# Bawah.net
KiCad netlist of a schematic drawn in EAGLE
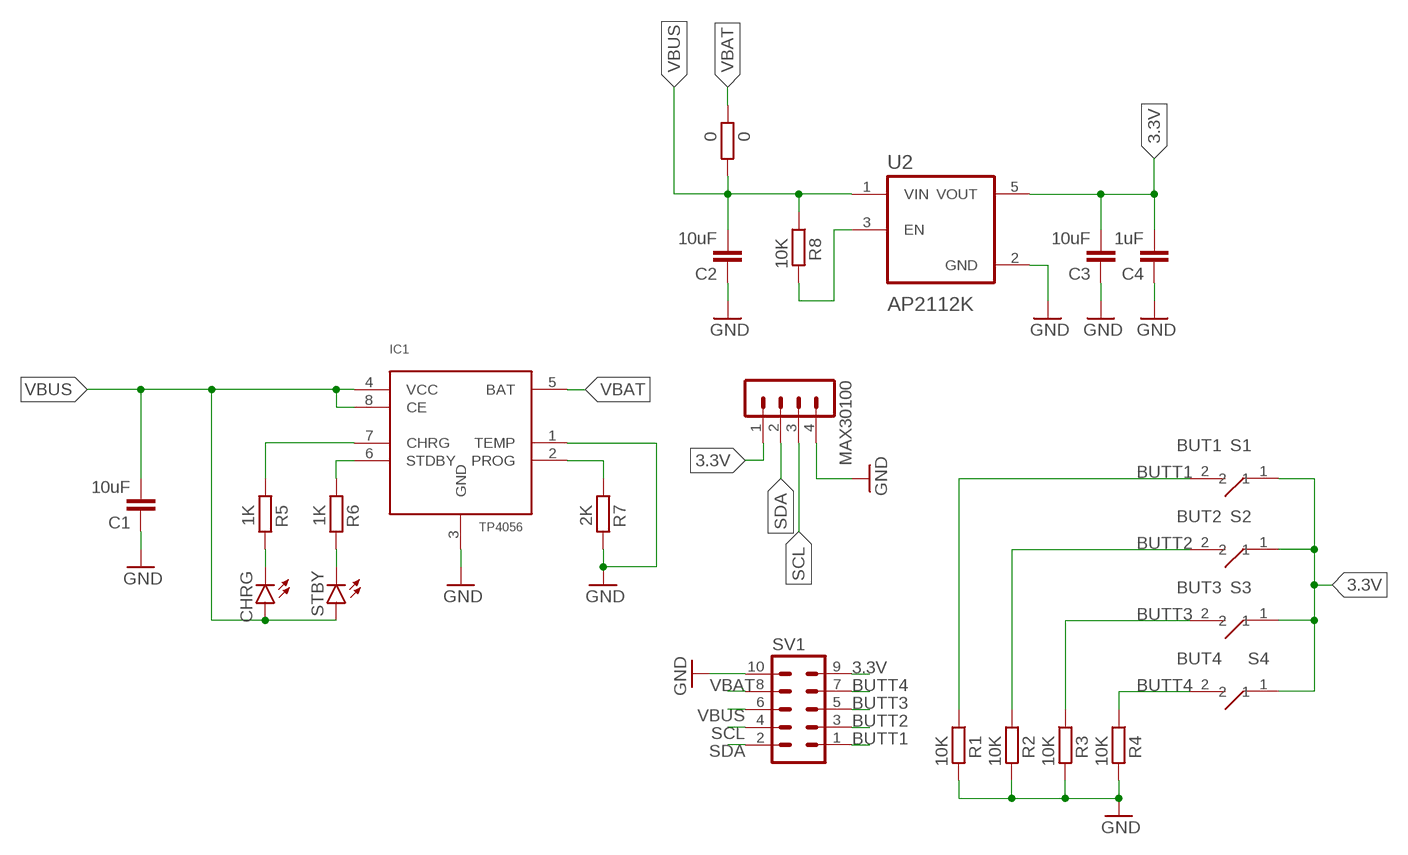
[diagram p0: schematic, sheet 1]

(export (version "E")
  (design (tool "Eeschema 10.0.6"))
  (components
    (comp (ref "0")
      (value "0")
      (footprint "eagle-import:R0805")
      (libsource (lib "eagle-import") (part "R-EU_R0805"))
    )
    (comp (ref "C1")
      (value "10uF")
      (footprint "eagle-import:C0805")
      (libsource (lib "eagle-import") (part "C-EUC0805"))
    )
    (comp (ref "C2")
      (value "10uF")
      (footprint "eagle-import:C0805")
      (libsource (lib "eagle-import") (part "C-EUC0805"))
    )
    (comp (ref "C3")
      (value "10uF")
      (footprint "eagle-import:C0805")
      (libsource (lib "eagle-import") (part "C-EUC0805"))
    )
    (comp (ref "C4")
      (value "1uF")
      (footprint "eagle-import:C0805")
      (libsource (lib "eagle-import") (part "C-EUC0805"))
    )
    (comp (ref "CHRG")
      (value "LEDCHIPLED_0805")
      (footprint "eagle-import:CHIPLED_0805")
      (libsource (lib "eagle-import") (part "LEDCHIPLED_0805"))
    )
    (comp (ref "IC1")
      (value "TP4056")
      (footprint "eagle-import:SOP-8")
      (fields (field (name "MF") "NanJing Top Power ASIC Corp.") (field (name "MP") "TP4056 "))
      (libsource (lib "eagle-import") (part "TP4056"))
    )
    (comp (ref "MAX30100")
      (value "MA04-1")
      (footprint "eagle-import:MA04-1")
      (libsource (lib "eagle-import") (part "MA04-1"))
    )
    (comp (ref "R1")
      (value "10K")
      (footprint "eagle-import:R0805")
      (libsource (lib "eagle-import") (part "R-EU_R0805"))
    )
    (comp (ref "R2")
      (value "10K")
      (footprint "eagle-import:R0805")
      (libsource (lib "eagle-import") (part "R-EU_R0805"))
    )
    (comp (ref "R3")
      (value "10K")
      (footprint "eagle-import:R0805")
      (libsource (lib "eagle-import") (part "R-EU_R0805"))
    )
    (comp (ref "R4")
      (value "10K")
      (footprint "eagle-import:R0805")
      (libsource (lib "eagle-import") (part "R-EU_R0805"))
    )
    (comp (ref "R5")
      (value "1K")
      (footprint "eagle-import:R0805")
      (libsource (lib "eagle-import") (part "R-EU_R0805"))
    )
    (comp (ref "R6")
      (value "1K")
      (footprint "eagle-import:R0805")
      (libsource (lib "eagle-import") (part "R-EU_R0805"))
    )
    (comp (ref "R7")
      (value "2K")
      (footprint "eagle-import:R0805")
      (libsource (lib "eagle-import") (part "R-EU_R0805"))
    )
    (comp (ref "R8")
      (value "10K")
      (footprint "eagle-import:R0805")
      (libsource (lib "eagle-import") (part "R-EU_R0805"))
    )
    (comp (ref "S1")
      (value "BUT1")
      (footprint "eagle-import:SIDE_SWITCH")
      (libsource (lib "eagle-import") (part "SIDE_SWITCH"))
    )
    (comp (ref "S2")
      (value "BUT2")
      (footprint "eagle-import:SIDE_SWITCH")
      (libsource (lib "eagle-import") (part "SIDE_SWITCH"))
    )
    (comp (ref "S3")
      (value "BUT3")
      (footprint "eagle-import:SIDE_SWITCH")
      (libsource (lib "eagle-import") (part "SIDE_SWITCH"))
    )
    (comp (ref "S4")
      (value "BUT4")
      (footprint "eagle-import:SIDE_SWITCH")
      (libsource (lib "eagle-import") (part "SIDE_SWITCH"))
    )
    (comp (ref "STBY")
      (value "LEDCHIPLED_0805")
      (footprint "eagle-import:CHIPLED_0805")
      (libsource (lib "eagle-import") (part "LEDCHIPLED_0805"))
    )
    (comp (ref "SV1")
      (value "MA05-2")
      (footprint "eagle-import:MA05-2")
      (libsource (lib "eagle-import") (part "MA05-2"))
    )
    (comp (ref "U2")
      (value "AP2112K")
      (footprint "eagle-import:SOT95P285X140-5N")
      (fields (field (name "MF") "Diodes Inc.") (field (name "MP") "AP2112K-3.3TRG1"))
      (libsource (lib "eagle-import") (part "AP2112K-3.3TRG1"))
    )
  )
  (nets
    (net (code "1") (name "/BUTT1") (class "Default")
      (node (ref "R1") (pin "1") (pinfunction "1_1") (pintype "passive"))
      (node (ref "S1") (pin "2") (pinfunction "1_2") (pintype "bidirectional"))
      (node (ref "SV1") (pin "1") (pinfunction "1_1") (pintype "passive"))
    )
    (net (code "2") (name "/BUTT2") (class "Default")
      (node (ref "R2") (pin "1") (pinfunction "1_1") (pintype "passive"))
      (node (ref "S2") (pin "2") (pinfunction "1_2") (pintype "bidirectional"))
      (node (ref "SV1") (pin "3") (pinfunction "3_3") (pintype "passive"))
    )
    (net (code "3") (name "/BUTT3") (class "Default")
      (node (ref "R3") (pin "1") (pinfunction "1_1") (pintype "passive"))
      (node (ref "S3") (pin "2") (pinfunction "1_2") (pintype "bidirectional"))
      (node (ref "SV1") (pin "5") (pinfunction "5_5") (pintype "passive"))
    )
    (net (code "4") (name "/BUTT4") (class "Default")
      (node (ref "R4") (pin "1") (pinfunction "1_1") (pintype "passive"))
      (node (ref "S4") (pin "2") (pinfunction "1_2") (pintype "bidirectional"))
      (node (ref "SV1") (pin "7") (pinfunction "7_7") (pintype "passive"))
    )
    (net (code "5") (name "3.3V") (class "Default")
      (node (ref "C3") (pin "2") (pinfunction "2_2") (pintype "passive"))
      (node (ref "C4") (pin "2") (pinfunction "2_2") (pintype "passive"))
      (node (ref "MAX30100") (pin "1") (pinfunction "1_1") (pintype "passive"))
      (node (ref "S1") (pin "1") (pinfunction "2_1") (pintype "bidirectional"))
      (node (ref "S2") (pin "1") (pinfunction "2_1") (pintype "bidirectional"))
      (node (ref "S3") (pin "1") (pinfunction "2_1") (pintype "bidirectional"))
      (node (ref "S4") (pin "1") (pinfunction "2_1") (pintype "bidirectional"))
      (node (ref "SV1") (pin "9") (pinfunction "9_9") (pintype "passive"))
      (node (ref "U2") (pin "5") (pinfunction "VOUT_5") (pintype "power_in"))
    )
    (net (code "6") (name "GND") (class "Default")
      (node (ref "C1") (pin "1") (pinfunction "1_1") (pintype "passive"))
      (node (ref "C2") (pin "1") (pinfunction "1_1") (pintype "passive"))
      (node (ref "C3") (pin "1") (pinfunction "1_1") (pintype "passive"))
      (node (ref "C4") (pin "1") (pinfunction "1_1") (pintype "passive"))
      (node (ref "IC1") (pin "1") (pinfunction "TEMP_1") (pintype "bidirectional"))
      (node (ref "IC1") (pin "3") (pinfunction "GND_3") (pintype "bidirectional"))
      (node (ref "MAX30100") (pin "4") (pinfunction "4_4") (pintype "passive"))
      (node (ref "R1") (pin "2") (pinfunction "2_2") (pintype "passive"))
      (node (ref "R2") (pin "2") (pinfunction "2_2") (pintype "passive"))
      (node (ref "R3") (pin "2") (pinfunction "2_2") (pintype "passive"))
      (node (ref "R4") (pin "2") (pinfunction "2_2") (pintype "passive"))
      (node (ref "R7") (pin "2") (pinfunction "2_2") (pintype "passive"))
      (node (ref "SV1") (pin "10") (pinfunction "10_10") (pintype "passive"))
      (node (ref "U2") (pin "2") (pinfunction "GND_2") (pintype "power_in"))
    )
    (net (code "7") (name "Net-(CHRG-PadC)") (class "Default")
      (node (ref "CHRG") (pin "C") (pinfunction "C_C") (pintype "passive"))
      (node (ref "R5") (pin "2") (pinfunction "2_2") (pintype "passive"))
    )
    (net (code "8") (name "Net-(IC1-CHRG)") (class "Default")
      (node (ref "IC1") (pin "7") (pinfunction "CHRG_7") (pintype "bidirectional"))
      (node (ref "R5") (pin "1") (pinfunction "1_1") (pintype "passive"))
    )
    (net (code "9") (name "Net-(IC1-PROG)") (class "Default")
      (node (ref "IC1") (pin "2") (pinfunction "PROG_2") (pintype "bidirectional"))
      (node (ref "R7") (pin "1") (pinfunction "1_1") (pintype "passive"))
    )
    (net (code "10") (name "Net-(IC1-STDBY)") (class "Default")
      (node (ref "IC1") (pin "6") (pinfunction "STDBY_6") (pintype "bidirectional"))
      (node (ref "R6") (pin "1") (pinfunction "1_1") (pintype "passive"))
    )
    (net (code "11") (name "Net-(R6-Pad2)") (class "Default")
      (node (ref "R6") (pin "2") (pinfunction "2_2") (pintype "passive"))
      (node (ref "STBY") (pin "C") (pinfunction "C_C") (pintype "passive"))
    )
    (net (code "12") (name "Net-(U2-EN)") (class "Default")
      (node (ref "R8") (pin "2") (pinfunction "2_2") (pintype "passive"))
      (node (ref "U2") (pin "3") (pinfunction "EN_3") (pintype "input"))
    )
    (net (code "13") (name "SCL") (class "Default")
      (node (ref "MAX30100") (pin "3") (pinfunction "3_3") (pintype "passive"))
      (node (ref "SV1") (pin "4") (pinfunction "4_4") (pintype "passive"))
    )
    (net (code "14") (name "SDA") (class "Default")
      (node (ref "MAX30100") (pin "2") (pinfunction "2_2") (pintype "passive"))
      (node (ref "SV1") (pin "2") (pinfunction "2_2") (pintype "passive"))
    )
    (net (code "15") (name "VBAT") (class "Default")
      (node (ref "0") (pin "1") (pinfunction "1_1") (pintype "passive"))
      (node (ref "IC1") (pin "5") (pinfunction "BAT_5") (pintype "bidirectional"))
      (node (ref "SV1") (pin "8") (pinfunction "8_8") (pintype "passive"))
    )
    (net (code "16") (name "VBUS") (class "Default")
      (node (ref "0") (pin "2") (pinfunction "2_2") (pintype "passive"))
      (node (ref "C1") (pin "2") (pinfunction "2_2") (pintype "passive"))
      (node (ref "C2") (pin "2") (pinfunction "2_2") (pintype "passive"))
      (node (ref "CHRG") (pin "A") (pinfunction "A_A") (pintype "passive"))
      (node (ref "IC1") (pin "4") (pinfunction "VCC_4") (pintype "bidirectional"))
      (node (ref "IC1") (pin "8") (pinfunction "CE_8") (pintype "bidirectional"))
      (node (ref "R8") (pin "1") (pinfunction "1_1") (pintype "passive"))
      (node (ref "STBY") (pin "A") (pinfunction "A_A") (pintype "passive"))
      (node (ref "SV1") (pin "6") (pinfunction "6_6") (pintype "passive"))
      (node (ref "U2") (pin "1") (pinfunction "VIN_1") (pintype "power_in"))
    )
  )
)
